# CMX655D_Audio_CODEC_PA.net
KiCad netlist of a schematic drawn in Altium Designer
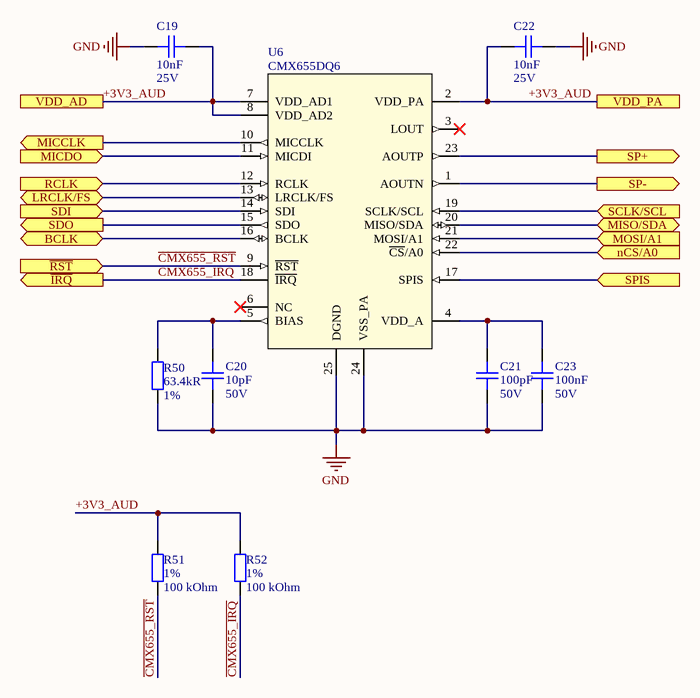
[diagram p0: CMX655D_Audio_CODEC_PA.SchDoc]

(export (version "E")
  (design (tool "Eeschema 10.0.6"))
  (components
    (comp (ref "C19")
      (value "CAP CER 10nF 25V X7R 10% 0402")
      (footprint "C0402")
      (description "Cap Cer 10nF 25V X7R 10% 0402")
      (fields
        (field (name "MANUFACTURER") "Kyocera AVX")
        (field (name "MANUFACTURER PART NUMBER") "04023C103KAT2A")
        (field (name "CAPACITANCE") "10nF")
        (field (name "VOLTAGE") "25V")
      )
      (libsource (lib "capacitors_smd") (part "CAP CER 10nF 25V X7R 10% 0402"))
    )
    (comp (ref "C20")
      (value "CAP CER 10PF 50V C0G/NP0 0402")
      (footprint "C0402")
      (description "10pF ±10% 50V Ceramic Capacitor C0G, NP0 0402 (1005 Metric)")
      (fields
        (field (name "MANUFACTURER") "KEMET")
        (field (name "MANUFACTURER PART NUMBER") "C0402C100K5GACTU")
        (field (name "CAPACITANCE") "10pF")
        (field (name "VOLTAGE RATING") "50V")
      )
      (libsource (lib "capacitors_smd") (part "CAP CER 10PF 50V C0G/NP0 0402"))
    )
    (comp (ref "C21")
      (value "CAP CER 100PF 50V C0G/NPO 0402")
      (footprint "C0402")
      (description "100pF ±5% 50V Ceramic Capacitor C0G, NP0 0402 (1005 Metric)")
      (fields
        (field (name "MANUFACTURER") "Yageo")
        (field (name "MANUFACTURER PART NUMBER") "CC0402JRNPO9BN101")
        (field (name "CAPACITANCE") "100pF")
        (field (name "VOLTAGE") "50V")
      )
      (libsource (lib "Control_Board_Model") (part "CAP CER 100PF 50V C0G/NPO 0402"))
    )
    (comp (ref "C22")
      (value "CAP CER 10nF 25V X7R 10% 0402")
      (footprint "C0402")
      (description "Cap Cer 10nF 25V X7R 10% 0402")
      (fields
        (field (name "MANUFACTURER") "Kyocera AVX")
        (field (name "MANUFACTURER PART NUMBER") "04023C103KAT2A")
        (field (name "CAPACITANCE") "10nF")
        (field (name "VOLTAGE") "25V")
      )
      (libsource (lib "capacitors_smd") (part "CAP CER 10nF 25V X7R 10% 0402"))
    )
    (comp (ref "C23")
      (value "CAP CER 0.1UF 50V X7R 0402")
      (footprint "C0402")
      (description "0.1µF ±10% 50V Ceramic Capacitor X7R 0402 (1005 Metric)")
      (fields
        (field (name "MANUFACTURER") "TDK")
        (field (name "MANUFACTURER PART NUMBER") "CGA2B3X7R1H104K050BB")
        (field (name "CAPACITANCE") "100nF")
        (field (name "VOLTAGE") "50V")
      )
      (libsource (lib "capacitors_smd") (part "CAP CER 0.1UF 50V X7R 0402"))
    )
    (comp (ref "R50")
      (value "RES SMD 63.4K OHM 1% 1/16W 0402")
      (footprint "R0402")
      (description "63.4 kOhms ±1% 0.063W, 1/16W Chip Resistor 0402 (1005 Metric) Moisture Resistant Thick Film")
      (fields
        (field (name "MANUFACTURER") "Yageo")
        (field (name "MANUFACTURER PART NUMBER") "RC0402FR-0763K4L")
        (field (name "RESISTANCE") "63.4kR")
        (field (name "TOLERANCE") "1%")
      )
      (libsource (lib "Control_Board_Model") (part "RES SMD 63.4K OHM 1% 1/16W 0402"))
    )
    (comp (ref "R51")
      (value "RES SMD 100K OHM 1% 1/16W 0402")
      (footprint "R0402")
      (description "100 kOhms ±1% 0.063W, 1/16W Chip Resistor 0402 (1005 Metric) Moisture Resistant Thick Film")
      (fields
        (field (name "MANUFACTURER") "Yageo")
        (field (name "MANUFACTURER PART NUMBER") "RC0402FR-07100KL")
        (field (name "TOLERANCE") "1%")
        (field (name "RESISTANCE") "100 kOhm")
      )
      (libsource (lib "Control_Board_Model") (part "RES SMD 100K OHM 1% 1/16W 0402"))
    )
    (comp (ref "R52")
      (value "RES SMD 100K OHM 1% 1/16W 0402")
      (footprint "R0402")
      (description "100 kOhms ±1% 0.063W, 1/16W Chip Resistor 0402 (1005 Metric) Moisture Resistant Thick Film")
      (fields
        (field (name "MANUFACTURER") "Yageo")
        (field (name "MANUFACTURER PART NUMBER") "RC0402FR-07100KL")
        (field (name "TOLERANCE") "1%")
        (field (name "RESISTANCE") "100 kOhm")
      )
      (libsource (lib "Control_Board_Model") (part "RES SMD 100K OHM 1% 1/16W 0402"))
    )
    (comp (ref "U6")
      (value "CMX655DQ6")
      (footprint "QFN50P400X400X100_HS-25N")
      (description "Voice-Band Interface 16 b I²S, PCM, SPI 24-VQFN (4x4)")
      (fields (field (name "MANUFACTURER") "CML Microcircuits"))
      (libsource (lib "BLDC_Motor_Driver") (part "IC CMX655DQ6-TR1K VOICE CODEC 16BIT 24VQFN"))
    )
  )
  (nets
    (net (code "1") (name "/+3V3_AUD") (class "Default")
      (node (ref "C19") (pin "2") (pinfunction "2_2") (pintype "passive"))
      (node (ref "C22") (pin "2") (pinfunction "2_2") (pintype "passive"))
      (node (ref "R51") (pin "2") (pinfunction "2_2") (pintype "passive"))
      (node (ref "R52") (pin "2") (pinfunction "2_2") (pintype "passive"))
      (node (ref "U6") (pin "2") (pinfunction "VDD_PA_2") (pintype "power_in"))
      (node (ref "U6") (pin "7") (pinfunction "VDD_AD1_7") (pintype "power_in"))
      (node (ref "U6") (pin "8") (pinfunction "VDD_AD2_8") (pintype "power_in"))
    )
    (net (code "2") (name "/BCLK") (class "Default")
      (node (ref "U6") (pin "16") (pinfunction "BCLK_16") (pintype "bidirectional"))
    )
    (net (code "3") (name "/CMX655_IRQ") (class "Default")
      (node (ref "R52") (pin "1") (pinfunction "1_1") (pintype "passive"))
      (node (ref "U6") (pin "18") (pinfunction "IRQ_18") (pintype "open_collector"))
    )
    (net (code "4") (name "/CMX655_RST") (class "Default")
      (node (ref "R51") (pin "1") (pinfunction "1_1") (pintype "passive"))
      (node (ref "U6") (pin "9") (pinfunction "RST_9") (pintype "input"))
    )
    (net (code "5") (name "/LRCLK{slash}FS") (class "Default")
      (node (ref "U6") (pin "13") (pinfunction "LRCLK/FS_13") (pintype "bidirectional"))
    )
    (net (code "6") (name "/MICCLK") (class "Default")
      (node (ref "U6") (pin "10") (pinfunction "MICCLK_10") (pintype "output"))
    )
    (net (code "7") (name "/MICDO") (class "Default")
      (node (ref "U6") (pin "11") (pinfunction "MICDI_11") (pintype "input"))
    )
    (net (code "8") (name "/MISO{slash}SDA") (class "Default")
      (node (ref "U6") (pin "20") (pinfunction "MISO/SDA_20") (pintype "bidirectional"))
    )
    (net (code "9") (name "/MOSI{slash}A1") (class "Default")
      (node (ref "U6") (pin "21") (pinfunction "MOSI/A1_21") (pintype "input"))
    )
    (net (code "10") (name "/RCLK") (class "Default")
      (node (ref "U6") (pin "12") (pinfunction "RCLK_12") (pintype "input"))
    )
    (net (code "11") (name "/SCLK{slash}SCL") (class "Default")
      (node (ref "U6") (pin "19") (pinfunction "SCLK/SCL_19") (pintype "input"))
    )
    (net (code "12") (name "/SDI") (class "Default")
      (node (ref "U6") (pin "14") (pinfunction "SDI_14") (pintype "input"))
    )
    (net (code "13") (name "/SDO") (class "Default")
      (node (ref "U6") (pin "15") (pinfunction "SDO_15") (pintype "output"))
    )
    (net (code "14") (name "/SP+") (class "Default")
      (node (ref "U6") (pin "23") (pinfunction "AOUTP_23") (pintype "output"))
    )
    (net (code "15") (name "/SP-") (class "Default")
      (node (ref "U6") (pin "1") (pinfunction "AOUTN_1") (pintype "output"))
    )
    (net (code "16") (name "/SPIS") (class "Default")
      (node (ref "U6") (pin "17") (pinfunction "SPIS_17") (pintype "input"))
    )
    (net (code "17") (name "/nCS{slash}A0") (class "Default")
      (node (ref "U6") (pin "22") (pinfunction "~{CS}/A0_22") (pintype "input"))
    )
    (net (code "18") (name "GND") (class "Default")
      (node (ref "C19") (pin "1") (pinfunction "1_1") (pintype "passive"))
      (node (ref "C20") (pin "1") (pinfunction "1_1") (pintype "passive"))
      (node (ref "C21") (pin "1") (pinfunction "1_1") (pintype "passive"))
      (node (ref "C22") (pin "1") (pinfunction "1_1") (pintype "passive"))
      (node (ref "C23") (pin "1") (pinfunction "1_1") (pintype "passive"))
      (node (ref "R50") (pin "2") (pinfunction "2_2") (pintype "passive"))
      (node (ref "U6") (pin "24") (pinfunction "VSS_PA_24") (pintype "power_in"))
      (node (ref "U6") (pin "25") (pinfunction "DGND_25") (pintype "power_in"))
    )
    (net (code "19") (name "Net-(U6-BIAS)") (class "Default")
      (node (ref "C20") (pin "2") (pinfunction "2_2") (pintype "passive"))
      (node (ref "R50") (pin "1") (pinfunction "1_1") (pintype "passive"))
      (node (ref "U6") (pin "5") (pinfunction "BIAS_5") (pintype "output"))
    )
    (net (code "20") (name "Net-(U6-VDD_A)") (class "Default")
      (node (ref "C21") (pin "2") (pinfunction "2_2") (pintype "passive"))
      (node (ref "C23") (pin "2") (pinfunction "2_2") (pintype "passive"))
      (node (ref "U6") (pin "4") (pinfunction "VDD_A_4") (pintype "power_in"))
    )
    (net (code "21") (name "unconnected-(U6-LOUT-Pad3)") (class "Default")
      (node (ref "U6") (pin "3") (pinfunction "LOUT_3") (pintype "output+no_connect"))
    )
    (net (code "22") (name "unconnected-(U6-NC-Pad6)") (class "Default")
      (node (ref "U6") (pin "6") (pinfunction "NC_6") (pintype "passive+no_connect"))
    )
  )
)
